# in14-4.net
KiCad netlist of a schematic drawn in EAGLE
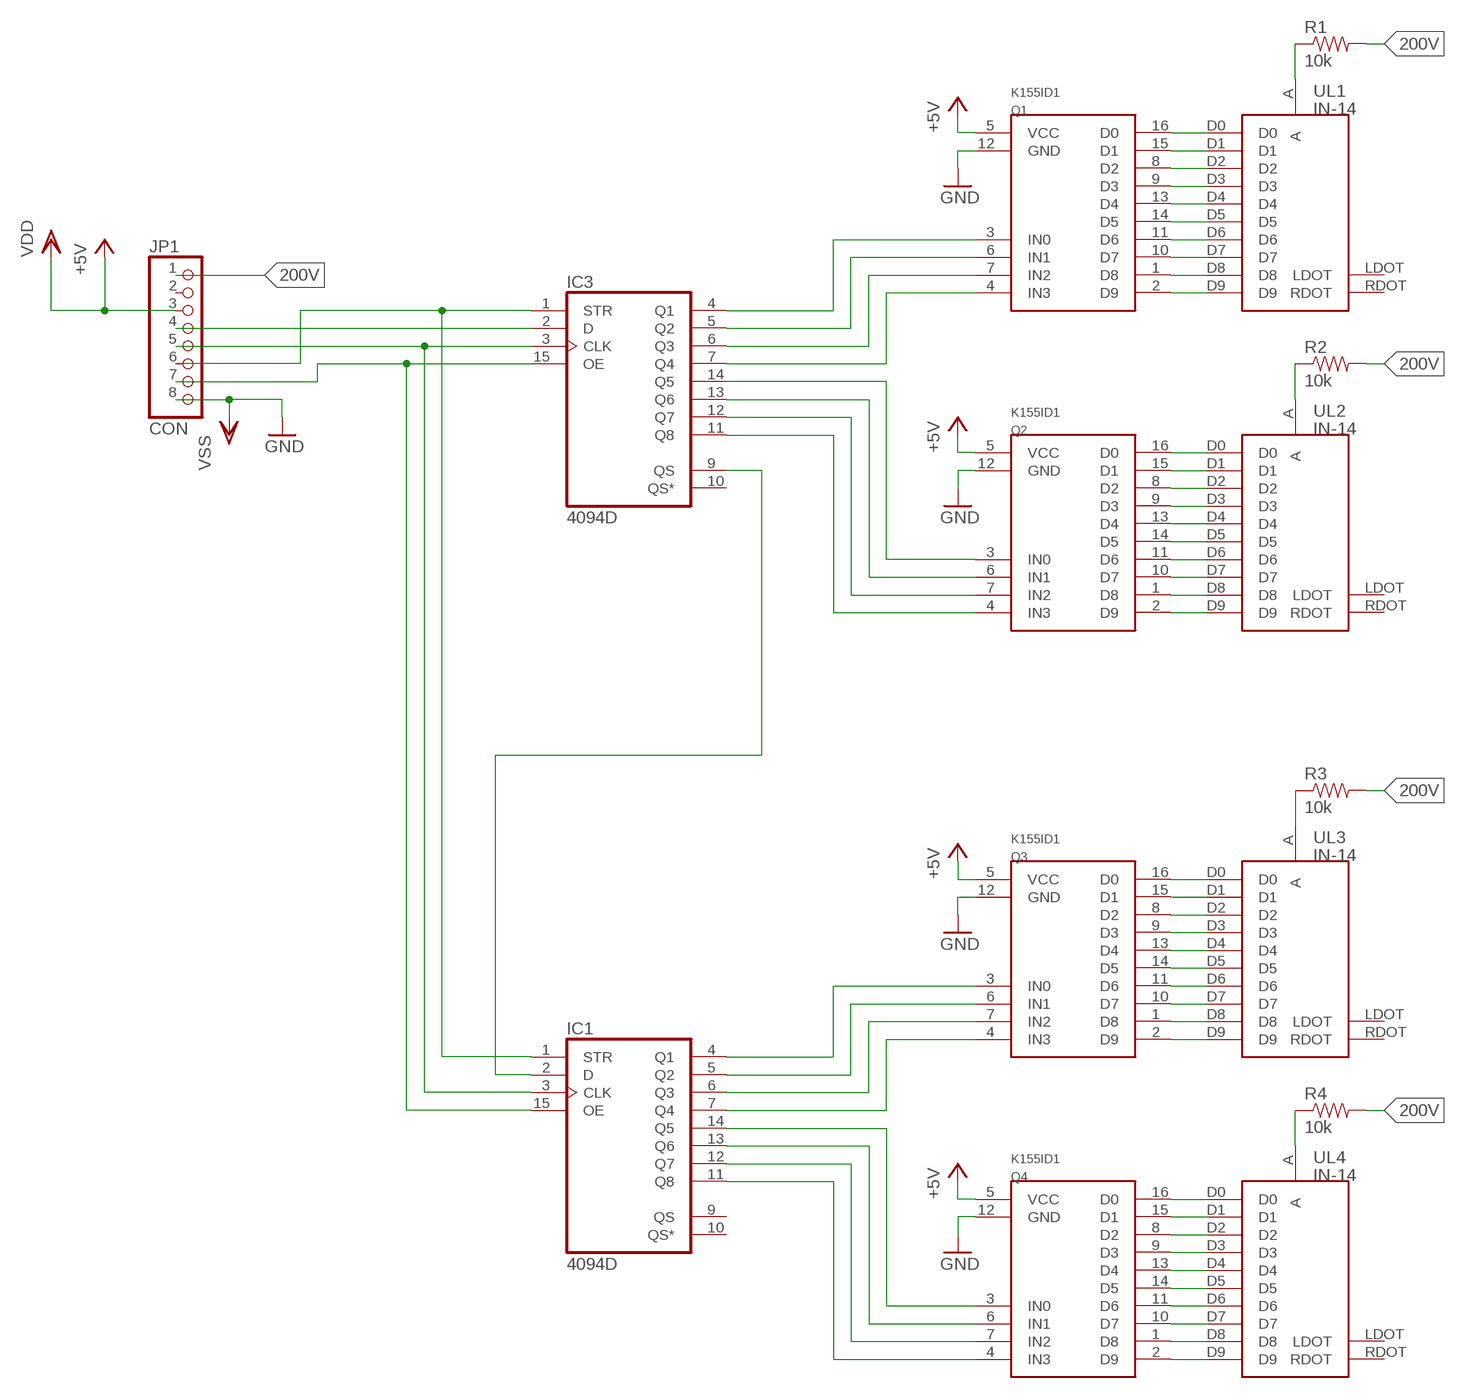
[diagram p0: schematic, sheet 1]

(export (version "E")
  (design (tool "Eeschema 10.0.6"))
  (components
    (comp (ref "IC1")
      (value "4094D")
      (footprint "eagle-import:SO16")
      (libsource (lib "eagle-import") (part "4094D"))
    )
    (comp (ref "IC3")
      (value "4094D")
      (footprint "eagle-import:SO16")
      (libsource (lib "eagle-import") (part "4094D"))
    )
    (comp (ref "JP1")
      (value "CON")
      (footprint "eagle-import:1X08")
      (libsource (lib "eagle-import") (part "PINHD-1X8"))
    )
    (comp (ref "Q1")
      (value "K155ID1")
      (footprint "eagle-import:DIL16")
      (libsource (lib "eagle-import") (part "K155ID1"))
    )
    (comp (ref "Q2")
      (value "K155ID1")
      (footprint "eagle-import:DIL16")
      (libsource (lib "eagle-import") (part "K155ID1"))
    )
    (comp (ref "Q3")
      (value "K155ID1")
      (footprint "eagle-import:DIL16")
      (libsource (lib "eagle-import") (part "K155ID1"))
    )
    (comp (ref "Q4")
      (value "K155ID1")
      (footprint "eagle-import:DIL16")
      (libsource (lib "eagle-import") (part "K155ID1"))
    )
    (comp (ref "R1")
      (value "10k")
      (footprint "eagle-import:1206")
      (libsource (lib "eagle-import") (part "RESISTOR1206"))
    )
    (comp (ref "R2")
      (value "10k")
      (footprint "eagle-import:1206")
      (libsource (lib "eagle-import") (part "RESISTOR1206"))
    )
    (comp (ref "R3")
      (value "10k")
      (footprint "eagle-import:1206")
      (libsource (lib "eagle-import") (part "RESISTOR1206"))
    )
    (comp (ref "R4")
      (value "10k")
      (footprint "eagle-import:1206")
      (libsource (lib "eagle-import") (part "RESISTOR1206"))
    )
    (comp (ref "UL1")
      (value "IN-14")
      (footprint "eagle-import:IN-14")
      (libsource (lib "eagle-import") (part "IN-14"))
    )
    (comp (ref "UL2")
      (value "IN-14")
      (footprint "eagle-import:IN-14")
      (libsource (lib "eagle-import") (part "IN-14"))
    )
    (comp (ref "UL3")
      (value "IN-14")
      (footprint "eagle-import:IN-14")
      (libsource (lib "eagle-import") (part "IN-14"))
    )
    (comp (ref "UL4")
      (value "IN-14")
      (footprint "eagle-import:IN-14")
      (libsource (lib "eagle-import") (part "IN-14"))
    )
  )
  (nets
    (net (code "1") (name "+5V") (class "Default")
      (node (ref "JP1") (pin "3") (pinfunction "3_3") (pintype "passive"))
      (node (ref "Q1") (pin "5") (pinfunction "VCC_5") (pintype "power_in"))
      (node (ref "Q2") (pin "5") (pinfunction "VCC_5") (pintype "power_in"))
      (node (ref "Q3") (pin "5") (pinfunction "VCC_5") (pintype "power_in"))
      (node (ref "Q4") (pin "5") (pinfunction "VCC_5") (pintype "power_in"))
    )
    (net (code "2") (name "200V") (class "Default")
      (node (ref "JP1") (pin "1") (pinfunction "1_1") (pintype "passive"))
      (node (ref "R1") (pin "2") (pinfunction "2_2") (pintype "passive"))
      (node (ref "R2") (pin "2") (pinfunction "2_2") (pintype "passive"))
      (node (ref "R3") (pin "2") (pinfunction "2_2") (pintype "passive"))
      (node (ref "R4") (pin "2") (pinfunction "2_2") (pintype "passive"))
    )
    (net (code "3") (name "GND") (class "Default")
      (node (ref "JP1") (pin "8") (pinfunction "8_8") (pintype "passive"))
      (node (ref "Q1") (pin "12") (pinfunction "GND_12") (pintype "power_in"))
      (node (ref "Q2") (pin "12") (pinfunction "GND_12") (pintype "power_in"))
      (node (ref "Q3") (pin "12") (pinfunction "GND_12") (pintype "power_in"))
      (node (ref "Q4") (pin "12") (pinfunction "GND_12") (pintype "power_in"))
    )
    (net (code "4") (name "Net-(IC1A-CLK)") (class "Default")
      (node (ref "IC1") (pin "3") (pinfunction "CLK_3") (pintype "input"))
      (node (ref "IC3") (pin "3") (pinfunction "CLK_3") (pintype "input"))
      (node (ref "JP1") (pin "5") (pinfunction "5_5") (pintype "passive"))
    )
    (net (code "5") (name "Net-(IC1A-D)") (class "Default")
      (node (ref "IC1") (pin "2") (pinfunction "D_2") (pintype "input"))
      (node (ref "IC3") (pin "9") (pinfunction "QS_9") (pintype "output"))
    )
    (net (code "6") (name "Net-(IC1A-OE)") (class "Default")
      (node (ref "IC1") (pin "15") (pinfunction "OE_15") (pintype "input"))
      (node (ref "IC3") (pin "15") (pinfunction "OE_15") (pintype "input"))
      (node (ref "JP1") (pin "7") (pinfunction "7_7") (pintype "passive"))
    )
    (net (code "7") (name "Net-(IC1A-Q1)") (class "Default")
      (node (ref "IC1") (pin "4") (pinfunction "Q1_4") (pintype "output"))
      (node (ref "Q3") (pin "3") (pinfunction "IN0_3") (pintype "input"))
    )
    (net (code "8") (name "Net-(IC1A-Q2)") (class "Default")
      (node (ref "IC1") (pin "5") (pinfunction "Q2_5") (pintype "output"))
      (node (ref "Q3") (pin "6") (pinfunction "IN1_6") (pintype "input"))
    )
    (net (code "9") (name "Net-(IC1A-Q3)") (class "Default")
      (node (ref "IC1") (pin "6") (pinfunction "Q3_6") (pintype "output"))
      (node (ref "Q3") (pin "7") (pinfunction "IN2_7") (pintype "input"))
    )
    (net (code "10") (name "Net-(IC1A-Q4)") (class "Default")
      (node (ref "IC1") (pin "7") (pinfunction "Q4_7") (pintype "output"))
      (node (ref "Q3") (pin "4") (pinfunction "IN3_4") (pintype "input"))
    )
    (net (code "11") (name "Net-(IC1A-Q5)") (class "Default")
      (node (ref "IC1") (pin "14") (pinfunction "Q5_14") (pintype "output"))
      (node (ref "Q4") (pin "3") (pinfunction "IN0_3") (pintype "input"))
    )
    (net (code "12") (name "Net-(IC1A-Q6)") (class "Default")
      (node (ref "IC1") (pin "13") (pinfunction "Q6_13") (pintype "output"))
      (node (ref "Q4") (pin "6") (pinfunction "IN1_6") (pintype "input"))
    )
    (net (code "13") (name "Net-(IC1A-Q7)") (class "Default")
      (node (ref "IC1") (pin "12") (pinfunction "Q7_12") (pintype "output"))
      (node (ref "Q4") (pin "7") (pinfunction "IN2_7") (pintype "input"))
    )
    (net (code "14") (name "Net-(IC1A-Q8)") (class "Default")
      (node (ref "IC1") (pin "11") (pinfunction "Q8_11") (pintype "output"))
      (node (ref "Q4") (pin "4") (pinfunction "IN3_4") (pintype "input"))
    )
    (net (code "15") (name "Net-(IC1A-STR)") (class "Default")
      (node (ref "IC1") (pin "1") (pinfunction "STR_1") (pintype "input"))
      (node (ref "IC3") (pin "1") (pinfunction "STR_1") (pintype "input"))
      (node (ref "JP1") (pin "6") (pinfunction "6_6") (pintype "passive"))
    )
    (net (code "16") (name "Net-(IC3A-D)") (class "Default")
      (node (ref "IC3") (pin "2") (pinfunction "D_2") (pintype "input"))
      (node (ref "JP1") (pin "4") (pinfunction "4_4") (pintype "passive"))
    )
    (net (code "17") (name "Net-(IC3A-Q1)") (class "Default")
      (node (ref "IC3") (pin "4") (pinfunction "Q1_4") (pintype "output"))
      (node (ref "Q1") (pin "3") (pinfunction "IN0_3") (pintype "input"))
    )
    (net (code "18") (name "Net-(IC3A-Q2)") (class "Default")
      (node (ref "IC3") (pin "5") (pinfunction "Q2_5") (pintype "output"))
      (node (ref "Q1") (pin "6") (pinfunction "IN1_6") (pintype "input"))
    )
    (net (code "19") (name "Net-(IC3A-Q3)") (class "Default")
      (node (ref "IC3") (pin "6") (pinfunction "Q3_6") (pintype "output"))
      (node (ref "Q1") (pin "7") (pinfunction "IN2_7") (pintype "input"))
    )
    (net (code "20") (name "Net-(IC3A-Q4)") (class "Default")
      (node (ref "IC3") (pin "7") (pinfunction "Q4_7") (pintype "output"))
      (node (ref "Q1") (pin "4") (pinfunction "IN3_4") (pintype "input"))
    )
    (net (code "21") (name "Net-(IC3A-Q5)") (class "Default")
      (node (ref "IC3") (pin "14") (pinfunction "Q5_14") (pintype "output"))
      (node (ref "Q2") (pin "3") (pinfunction "IN0_3") (pintype "input"))
    )
    (net (code "22") (name "Net-(IC3A-Q6)") (class "Default")
      (node (ref "IC3") (pin "13") (pinfunction "Q6_13") (pintype "output"))
      (node (ref "Q2") (pin "6") (pinfunction "IN1_6") (pintype "input"))
    )
    (net (code "23") (name "Net-(IC3A-Q7)") (class "Default")
      (node (ref "IC3") (pin "12") (pinfunction "Q7_12") (pintype "output"))
      (node (ref "Q2") (pin "7") (pinfunction "IN2_7") (pintype "input"))
    )
    (net (code "24") (name "Net-(IC3A-Q8)") (class "Default")
      (node (ref "IC3") (pin "11") (pinfunction "Q8_11") (pintype "output"))
      (node (ref "Q2") (pin "4") (pinfunction "IN3_4") (pintype "input"))
    )
    (net (code "25") (name "Net-(Q1-D0)") (class "Default")
      (node (ref "Q1") (pin "16") (pinfunction "D0_16") (pintype "output"))
      (node (ref "UL1") (pin "D0") (pinfunction "D0_D0") (pintype "bidirectional"))
    )
    (net (code "26") (name "Net-(Q1-D1)") (class "Default")
      (node (ref "Q1") (pin "15") (pinfunction "D1_15") (pintype "output"))
      (node (ref "UL1") (pin "D1") (pinfunction "D1_D1") (pintype "bidirectional"))
    )
    (net (code "27") (name "Net-(Q1-D2)") (class "Default")
      (node (ref "Q1") (pin "8") (pinfunction "D2_8") (pintype "output"))
      (node (ref "UL1") (pin "D2") (pinfunction "D2_D2") (pintype "bidirectional"))
    )
    (net (code "28") (name "Net-(Q1-D3)") (class "Default")
      (node (ref "Q1") (pin "9") (pinfunction "D3_9") (pintype "output"))
      (node (ref "UL1") (pin "D3") (pinfunction "D3_D3") (pintype "bidirectional"))
    )
    (net (code "29") (name "Net-(Q1-D4)") (class "Default")
      (node (ref "Q1") (pin "13") (pinfunction "D4_13") (pintype "output"))
      (node (ref "UL1") (pin "D4") (pinfunction "D4_D4") (pintype "bidirectional"))
    )
    (net (code "30") (name "Net-(Q1-D5)") (class "Default")
      (node (ref "Q1") (pin "14") (pinfunction "D5_14") (pintype "output"))
      (node (ref "UL1") (pin "D5") (pinfunction "D5_D5") (pintype "bidirectional"))
    )
    (net (code "31") (name "Net-(Q1-D6)") (class "Default")
      (node (ref "Q1") (pin "11") (pinfunction "D6_11") (pintype "output"))
      (node (ref "UL1") (pin "D6") (pinfunction "D6_D6") (pintype "bidirectional"))
    )
    (net (code "32") (name "Net-(Q1-D7)") (class "Default")
      (node (ref "Q1") (pin "10") (pinfunction "D7_10") (pintype "output"))
      (node (ref "UL1") (pin "D7") (pinfunction "D7_D7") (pintype "bidirectional"))
    )
    (net (code "33") (name "Net-(Q1-D8)") (class "Default")
      (node (ref "Q1") (pin "1") (pinfunction "D8_1") (pintype "output"))
      (node (ref "UL1") (pin "D8") (pinfunction "D8_D8") (pintype "bidirectional"))
    )
    (net (code "34") (name "Net-(Q1-D9)") (class "Default")
      (node (ref "Q1") (pin "2") (pinfunction "D9_2") (pintype "output"))
      (node (ref "UL1") (pin "D9") (pinfunction "D9_D9") (pintype "bidirectional"))
    )
    (net (code "35") (name "Net-(Q2-D0)") (class "Default")
      (node (ref "Q2") (pin "16") (pinfunction "D0_16") (pintype "output"))
      (node (ref "UL2") (pin "D0") (pinfunction "D0_D0") (pintype "bidirectional"))
    )
    (net (code "36") (name "Net-(Q2-D1)") (class "Default")
      (node (ref "Q2") (pin "15") (pinfunction "D1_15") (pintype "output"))
      (node (ref "UL2") (pin "D1") (pinfunction "D1_D1") (pintype "bidirectional"))
    )
    (net (code "37") (name "Net-(Q2-D2)") (class "Default")
      (node (ref "Q2") (pin "8") (pinfunction "D2_8") (pintype "output"))
      (node (ref "UL2") (pin "D2") (pinfunction "D2_D2") (pintype "bidirectional"))
    )
    (net (code "38") (name "Net-(Q2-D3)") (class "Default")
      (node (ref "Q2") (pin "9") (pinfunction "D3_9") (pintype "output"))
      (node (ref "UL2") (pin "D3") (pinfunction "D3_D3") (pintype "bidirectional"))
    )
    (net (code "39") (name "Net-(Q2-D4)") (class "Default")
      (node (ref "Q2") (pin "13") (pinfunction "D4_13") (pintype "output"))
      (node (ref "UL2") (pin "D4") (pinfunction "D4_D4") (pintype "bidirectional"))
    )
    (net (code "40") (name "Net-(Q2-D5)") (class "Default")
      (node (ref "Q2") (pin "14") (pinfunction "D5_14") (pintype "output"))
      (node (ref "UL2") (pin "D5") (pinfunction "D5_D5") (pintype "bidirectional"))
    )
    (net (code "41") (name "Net-(Q2-D6)") (class "Default")
      (node (ref "Q2") (pin "11") (pinfunction "D6_11") (pintype "output"))
      (node (ref "UL2") (pin "D6") (pinfunction "D6_D6") (pintype "bidirectional"))
    )
    (net (code "42") (name "Net-(Q2-D7)") (class "Default")
      (node (ref "Q2") (pin "10") (pinfunction "D7_10") (pintype "output"))
      (node (ref "UL2") (pin "D7") (pinfunction "D7_D7") (pintype "bidirectional"))
    )
    (net (code "43") (name "Net-(Q2-D8)") (class "Default")
      (node (ref "Q2") (pin "1") (pinfunction "D8_1") (pintype "output"))
      (node (ref "UL2") (pin "D8") (pinfunction "D8_D8") (pintype "bidirectional"))
    )
    (net (code "44") (name "Net-(Q2-D9)") (class "Default")
      (node (ref "Q2") (pin "2") (pinfunction "D9_2") (pintype "output"))
      (node (ref "UL2") (pin "D9") (pinfunction "D9_D9") (pintype "bidirectional"))
    )
    (net (code "45") (name "Net-(Q3-D0)") (class "Default")
      (node (ref "Q3") (pin "16") (pinfunction "D0_16") (pintype "output"))
      (node (ref "UL3") (pin "D0") (pinfunction "D0_D0") (pintype "bidirectional"))
    )
    (net (code "46") (name "Net-(Q3-D1)") (class "Default")
      (node (ref "Q3") (pin "15") (pinfunction "D1_15") (pintype "output"))
      (node (ref "UL3") (pin "D1") (pinfunction "D1_D1") (pintype "bidirectional"))
    )
    (net (code "47") (name "Net-(Q3-D2)") (class "Default")
      (node (ref "Q3") (pin "8") (pinfunction "D2_8") (pintype "output"))
      (node (ref "UL3") (pin "D2") (pinfunction "D2_D2") (pintype "bidirectional"))
    )
    (net (code "48") (name "Net-(Q3-D3)") (class "Default")
      (node (ref "Q3") (pin "9") (pinfunction "D3_9") (pintype "output"))
      (node (ref "UL3") (pin "D3") (pinfunction "D3_D3") (pintype "bidirectional"))
    )
    (net (code "49") (name "Net-(Q3-D4)") (class "Default")
      (node (ref "Q3") (pin "13") (pinfunction "D4_13") (pintype "output"))
      (node (ref "UL3") (pin "D4") (pinfunction "D4_D4") (pintype "bidirectional"))
    )
    (net (code "50") (name "Net-(Q3-D5)") (class "Default")
      (node (ref "Q3") (pin "14") (pinfunction "D5_14") (pintype "output"))
      (node (ref "UL3") (pin "D5") (pinfunction "D5_D5") (pintype "bidirectional"))
    )
    (net (code "51") (name "Net-(Q3-D6)") (class "Default")
      (node (ref "Q3") (pin "11") (pinfunction "D6_11") (pintype "output"))
      (node (ref "UL3") (pin "D6") (pinfunction "D6_D6") (pintype "bidirectional"))
    )
    (net (code "52") (name "Net-(Q3-D7)") (class "Default")
      (node (ref "Q3") (pin "10") (pinfunction "D7_10") (pintype "output"))
      (node (ref "UL3") (pin "D7") (pinfunction "D7_D7") (pintype "bidirectional"))
    )
    (net (code "53") (name "Net-(Q3-D8)") (class "Default")
      (node (ref "Q3") (pin "1") (pinfunction "D8_1") (pintype "output"))
      (node (ref "UL3") (pin "D8") (pinfunction "D8_D8") (pintype "bidirectional"))
    )
    (net (code "54") (name "Net-(Q3-D9)") (class "Default")
      (node (ref "Q3") (pin "2") (pinfunction "D9_2") (pintype "output"))
      (node (ref "UL3") (pin "D9") (pinfunction "D9_D9") (pintype "bidirectional"))
    )
    (net (code "55") (name "Net-(Q4-D0)") (class "Default")
      (node (ref "Q4") (pin "16") (pinfunction "D0_16") (pintype "output"))
      (node (ref "UL4") (pin "D0") (pinfunction "D0_D0") (pintype "bidirectional"))
    )
    (net (code "56") (name "Net-(Q4-D1)") (class "Default")
      (node (ref "Q4") (pin "15") (pinfunction "D1_15") (pintype "output"))
      (node (ref "UL4") (pin "D1") (pinfunction "D1_D1") (pintype "bidirectional"))
    )
    (net (code "57") (name "Net-(Q4-D2)") (class "Default")
      (node (ref "Q4") (pin "8") (pinfunction "D2_8") (pintype "output"))
      (node (ref "UL4") (pin "D2") (pinfunction "D2_D2") (pintype "bidirectional"))
    )
    (net (code "58") (name "Net-(Q4-D3)") (class "Default")
      (node (ref "Q4") (pin "9") (pinfunction "D3_9") (pintype "output"))
      (node (ref "UL4") (pin "D3") (pinfunction "D3_D3") (pintype "bidirectional"))
    )
    (net (code "59") (name "Net-(Q4-D4)") (class "Default")
      (node (ref "Q4") (pin "13") (pinfunction "D4_13") (pintype "output"))
      (node (ref "UL4") (pin "D4") (pinfunction "D4_D4") (pintype "bidirectional"))
    )
    (net (code "60") (name "Net-(Q4-D5)") (class "Default")
      (node (ref "Q4") (pin "14") (pinfunction "D5_14") (pintype "output"))
      (node (ref "UL4") (pin "D5") (pinfunction "D5_D5") (pintype "bidirectional"))
    )
    (net (code "61") (name "Net-(Q4-D6)") (class "Default")
      (node (ref "Q4") (pin "11") (pinfunction "D6_11") (pintype "output"))
      (node (ref "UL4") (pin "D6") (pinfunction "D6_D6") (pintype "bidirectional"))
    )
    (net (code "62") (name "Net-(Q4-D7)") (class "Default")
      (node (ref "Q4") (pin "10") (pinfunction "D7_10") (pintype "output"))
      (node (ref "UL4") (pin "D7") (pinfunction "D7_D7") (pintype "bidirectional"))
    )
    (net (code "63") (name "Net-(Q4-D8)") (class "Default")
      (node (ref "Q4") (pin "1") (pinfunction "D8_1") (pintype "output"))
      (node (ref "UL4") (pin "D8") (pinfunction "D8_D8") (pintype "bidirectional"))
    )
    (net (code "64") (name "Net-(Q4-D9)") (class "Default")
      (node (ref "Q4") (pin "2") (pinfunction "D9_2") (pintype "output"))
      (node (ref "UL4") (pin "D9") (pinfunction "D9_D9") (pintype "bidirectional"))
    )
    (net (code "65") (name "Net-(R1-Pad1)") (class "Default")
      (node (ref "R1") (pin "1") (pinfunction "1_1") (pintype "passive"))
      (node (ref "UL1") (pin "A") (pinfunction "A_A") (pintype "bidirectional"))
    )
    (net (code "66") (name "Net-(R2-Pad1)") (class "Default")
      (node (ref "R2") (pin "1") (pinfunction "1_1") (pintype "passive"))
      (node (ref "UL2") (pin "A") (pinfunction "A_A") (pintype "bidirectional"))
    )
    (net (code "67") (name "Net-(R3-Pad1)") (class "Default")
      (node (ref "R3") (pin "1") (pinfunction "1_1") (pintype "passive"))
      (node (ref "UL3") (pin "A") (pinfunction "A_A") (pintype "bidirectional"))
    )
    (net (code "68") (name "Net-(R4-Pad1)") (class "Default")
      (node (ref "R4") (pin "1") (pinfunction "1_1") (pintype "passive"))
      (node (ref "UL4") (pin "A") (pinfunction "A_A") (pintype "bidirectional"))
    )
    (net (code "69") (name "unconnected-(IC1A-QS*-Pad10)") (class "Default")
      (node (ref "IC1") (pin "10") (pinfunction "QS*_10") (pintype "output"))
    )
    (net (code "70") (name "unconnected-(IC1A-QS-Pad9)") (class "Default")
      (node (ref "IC1") (pin "9") (pinfunction "QS_9") (pintype "output"))
    )
    (net (code "71") (name "unconnected-(IC3A-QS*-Pad10)") (class "Default")
      (node (ref "IC3") (pin "10") (pinfunction "QS*_10") (pintype "output"))
    )
    (net (code "72") (name "unconnected-(JP1-Pad2)") (class "Default")
      (node (ref "JP1") (pin "2") (pinfunction "2_2") (pintype "passive"))
    )
    (net (code "73") (name "unconnected-(UL1-PadLDOT)") (class "Default")
      (node (ref "UL1") (pin "LDOT") (pinfunction "LDOT_LDOT") (pintype "bidirectional"))
    )
    (net (code "74") (name "unconnected-(UL1-PadRDOT)") (class "Default")
      (node (ref "UL1") (pin "RDOT") (pinfunction "RDOT_RDOT") (pintype "bidirectional"))
    )
    (net (code "75") (name "unconnected-(UL2-PadLDOT)") (class "Default")
      (node (ref "UL2") (pin "LDOT") (pinfunction "LDOT_LDOT") (pintype "bidirectional"))
    )
    (net (code "76") (name "unconnected-(UL2-PadRDOT)") (class "Default")
      (node (ref "UL2") (pin "RDOT") (pinfunction "RDOT_RDOT") (pintype "bidirectional"))
    )
    (net (code "77") (name "unconnected-(UL3-PadLDOT)") (class "Default")
      (node (ref "UL3") (pin "LDOT") (pinfunction "LDOT_LDOT") (pintype "bidirectional"))
    )
    (net (code "78") (name "unconnected-(UL3-PadRDOT)") (class "Default")
      (node (ref "UL3") (pin "RDOT") (pinfunction "RDOT_RDOT") (pintype "bidirectional"))
    )
    (net (code "79") (name "unconnected-(UL4-PadLDOT)") (class "Default")
      (node (ref "UL4") (pin "LDOT") (pinfunction "LDOT_LDOT") (pintype "bidirectional"))
    )
    (net (code "80") (name "unconnected-(UL4-PadRDOT)") (class "Default")
      (node (ref "UL4") (pin "RDOT") (pinfunction "RDOT_RDOT") (pintype "bidirectional"))
    )
  )
)
